# io-ok.net
KiCad netlist of a schematic drawn in EAGLE
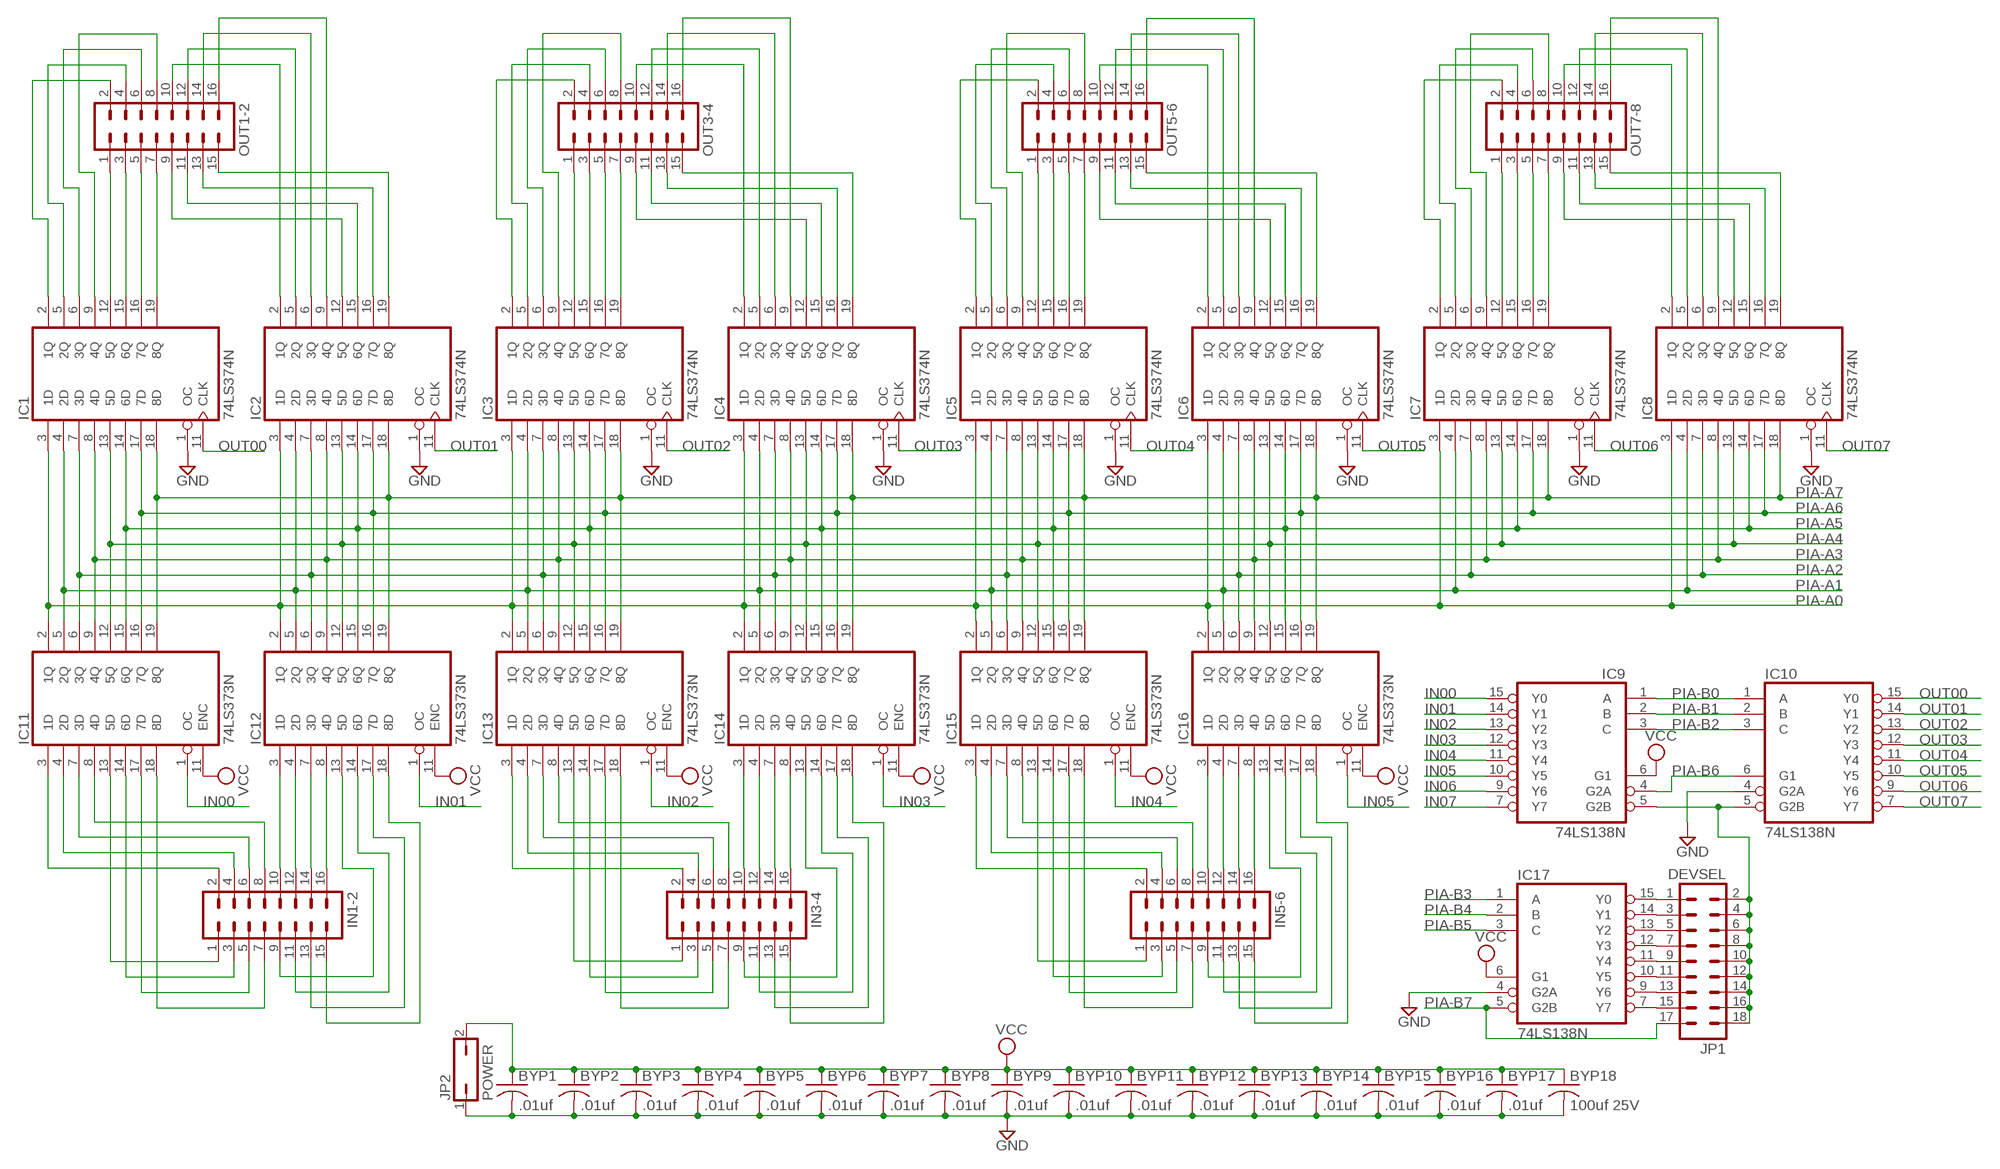
[diagram p0: schematic, sheet 1]
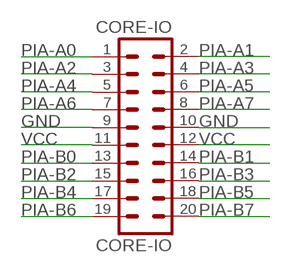
[diagram p1: schematic, sheet 2]

(export (version "E")
  (design (tool "Eeschema 10.0.6"))
  (components
    (comp (ref "CORE-IO")
      (value "CORE-IO")
      (footprint "eagle-import:MA10-2")
      (libsource (lib "eagle-import") (part "MA10-2"))
    )
    (comp (ref "BYP1")
      (value ".01uf")
      (footprint "eagle-import:C050-025X075")
      (libsource (lib "eagle-import") (part "C-US050-025X075"))
    )
    (comp (ref "BYP2")
      (value ".01uf")
      (footprint "eagle-import:C050-025X075")
      (libsource (lib "eagle-import") (part "C-US050-025X075"))
    )
    (comp (ref "BYP3")
      (value ".01uf")
      (footprint "eagle-import:C050-025X075")
      (libsource (lib "eagle-import") (part "C-US050-025X075"))
    )
    (comp (ref "BYP4")
      (value ".01uf")
      (footprint "eagle-import:C050-025X075")
      (libsource (lib "eagle-import") (part "C-US050-025X075"))
    )
    (comp (ref "BYP5")
      (value ".01uf")
      (footprint "eagle-import:C050-025X075")
      (libsource (lib "eagle-import") (part "C-US050-025X075"))
    )
    (comp (ref "BYP6")
      (value ".01uf")
      (footprint "eagle-import:C050-025X075")
      (libsource (lib "eagle-import") (part "C-US050-025X075"))
    )
    (comp (ref "BYP7")
      (value ".01uf")
      (footprint "eagle-import:C050-025X075")
      (libsource (lib "eagle-import") (part "C-US050-025X075"))
    )
    (comp (ref "BYP8")
      (value ".01uf")
      (footprint "eagle-import:C050-025X075")
      (libsource (lib "eagle-import") (part "C-US050-025X075"))
    )
    (comp (ref "BYP9")
      (value ".01uf")
      (footprint "eagle-import:C050-025X075")
      (libsource (lib "eagle-import") (part "C-US050-025X075"))
    )
    (comp (ref "BYP10")
      (value ".01uf")
      (footprint "eagle-import:C050-025X075")
      (libsource (lib "eagle-import") (part "C-US050-025X075"))
    )
    (comp (ref "BYP11")
      (value ".01uf")
      (footprint "eagle-import:C050-025X075")
      (libsource (lib "eagle-import") (part "C-US050-025X075"))
    )
    (comp (ref "BYP12")
      (value ".01uf")
      (footprint "eagle-import:C050-025X075")
      (libsource (lib "eagle-import") (part "C-US050-025X075"))
    )
    (comp (ref "BYP13")
      (value ".01uf")
      (footprint "eagle-import:C050-025X075")
      (libsource (lib "eagle-import") (part "C-US050-025X075"))
    )
    (comp (ref "BYP14")
      (value ".01uf")
      (footprint "eagle-import:C050-025X075")
      (libsource (lib "eagle-import") (part "C-US050-025X075"))
    )
    (comp (ref "BYP15")
      (value ".01uf")
      (footprint "eagle-import:C050-025X075")
      (libsource (lib "eagle-import") (part "C-US050-025X075"))
    )
    (comp (ref "BYP16")
      (value ".01uf")
      (footprint "eagle-import:C050-025X075")
      (libsource (lib "eagle-import") (part "C-US050-025X075"))
    )
    (comp (ref "BYP17")
      (value ".01uf")
      (footprint "eagle-import:C050-025X075")
      (libsource (lib "eagle-import") (part "C-US050-025X075"))
    )
    (comp (ref "BYP18")
      (value "100uf 25V")
      (footprint "eagle-import:C150-064X183")
      (libsource (lib "eagle-import") (part "C-US150-064X183"))
    )
    (comp (ref "IC1")
      (value "74LS374N")
      (footprint "eagle-import:DIL20")
      (libsource (lib "eagle-import") (part "74374NLS"))
    )
    (comp (ref "IC2")
      (value "74LS374N")
      (footprint "eagle-import:DIL20")
      (libsource (lib "eagle-import") (part "74374NLS"))
    )
    (comp (ref "IC3")
      (value "74LS374N")
      (footprint "eagle-import:DIL20")
      (libsource (lib "eagle-import") (part "74374NLS"))
    )
    (comp (ref "IC4")
      (value "74LS374N")
      (footprint "eagle-import:DIL20")
      (libsource (lib "eagle-import") (part "74374NLS"))
    )
    (comp (ref "IC5")
      (value "74LS374N")
      (footprint "eagle-import:DIL20")
      (libsource (lib "eagle-import") (part "74374NLS"))
    )
    (comp (ref "IC6")
      (value "74LS374N")
      (footprint "eagle-import:DIL20")
      (libsource (lib "eagle-import") (part "74374NLS"))
    )
    (comp (ref "IC7")
      (value "74LS374N")
      (footprint "eagle-import:DIL20")
      (libsource (lib "eagle-import") (part "74374NLS"))
    )
    (comp (ref "IC8")
      (value "74LS374N")
      (footprint "eagle-import:DIL20")
      (libsource (lib "eagle-import") (part "74374NLS"))
    )
    (comp (ref "IC9")
      (value "74LS138N")
      (footprint "eagle-import:DIL16")
      (libsource (lib "eagle-import") (part "74138NLS"))
    )
    (comp (ref "IC10")
      (value "74LS138N")
      (footprint "eagle-import:DIL16")
      (libsource (lib "eagle-import") (part "74138NLS"))
    )
    (comp (ref "IC11")
      (value "74LS373N")
      (footprint "eagle-import:DIL20")
      (libsource (lib "eagle-import") (part "74373NLS"))
    )
    (comp (ref "IC12")
      (value "74LS373N")
      (footprint "eagle-import:DIL20")
      (libsource (lib "eagle-import") (part "74373NLS"))
    )
    (comp (ref "IC13")
      (value "74LS373N")
      (footprint "eagle-import:DIL20")
      (libsource (lib "eagle-import") (part "74373NLS"))
    )
    (comp (ref "IC14")
      (value "74LS373N")
      (footprint "eagle-import:DIL20")
      (libsource (lib "eagle-import") (part "74373NLS"))
    )
    (comp (ref "IC15")
      (value "74LS373N")
      (footprint "eagle-import:DIL20")
      (libsource (lib "eagle-import") (part "74373NLS"))
    )
    (comp (ref "IC16")
      (value "74LS373N")
      (footprint "eagle-import:DIL20")
      (libsource (lib "eagle-import") (part "74373NLS"))
    )
    (comp (ref "IC17")
      (value "74LS138N")
      (footprint "eagle-import:DIL16")
      (libsource (lib "eagle-import") (part "74138NLS"))
    )
    (comp (ref "IN1-2")
      (value "MA08-2")
      (footprint "eagle-import:MA08-2")
      (libsource (lib "eagle-import") (part "MA08-2"))
    )
    (comp (ref "IN3-4")
      (value "MA08-2")
      (footprint "eagle-import:MA08-2")
      (libsource (lib "eagle-import") (part "MA08-2"))
    )
    (comp (ref "IN5-6")
      (value "MA08-2")
      (footprint "eagle-import:MA08-2")
      (libsource (lib "eagle-import") (part "MA08-2"))
    )
    (comp (ref "JP1")
      (value "DEVSEL")
      (footprint "eagle-import:MA09-2")
      (libsource (lib "eagle-import") (part "MA09-2"))
    )
    (comp (ref "JP2")
      (value "POWER")
      (footprint "eagle-import:JP1")
      (libsource (lib "eagle-import") (part "JP1Q"))
    )
    (comp (ref "OUT1-2")
      (value "MA08-2")
      (footprint "eagle-import:MA08-2")
      (libsource (lib "eagle-import") (part "MA08-2"))
    )
    (comp (ref "OUT3-4")
      (value "MA08-2")
      (footprint "eagle-import:MA08-2")
      (libsource (lib "eagle-import") (part "MA08-2"))
    )
    (comp (ref "OUT5-6")
      (value "MA08-2")
      (footprint "eagle-import:MA08-2")
      (libsource (lib "eagle-import") (part "MA08-2"))
    )
    (comp (ref "OUT7-8")
      (value "MA08-2")
      (footprint "eagle-import:MA08-2")
      (libsource (lib "eagle-import") (part "MA08-2"))
    )
  )
  (nets
    (net (code "1") (name "GND") (class "Default")
      (node (ref "BYP1") (pin "2") (pinfunction "2_2") (pintype "passive"))
      (node (ref "BYP10") (pin "2") (pinfunction "2_2") (pintype "passive"))
      (node (ref "BYP11") (pin "2") (pinfunction "2_2") (pintype "passive"))
      (node (ref "BYP12") (pin "2") (pinfunction "2_2") (pintype "passive"))
      (node (ref "BYP13") (pin "2") (pinfunction "2_2") (pintype "passive"))
      (node (ref "BYP14") (pin "2") (pinfunction "2_2") (pintype "passive"))
      (node (ref "BYP15") (pin "2") (pinfunction "2_2") (pintype "passive"))
      (node (ref "BYP16") (pin "2") (pinfunction "2_2") (pintype "passive"))
      (node (ref "BYP17") (pin "2") (pinfunction "2_2") (pintype "passive"))
      (node (ref "BYP18") (pin "2") (pinfunction "2_2") (pintype "passive"))
      (node (ref "BYP2") (pin "2") (pinfunction "2_2") (pintype "passive"))
      (node (ref "BYP3") (pin "2") (pinfunction "2_2") (pintype "passive"))
      (node (ref "BYP4") (pin "2") (pinfunction "2_2") (pintype "passive"))
      (node (ref "BYP5") (pin "2") (pinfunction "2_2") (pintype "passive"))
      (node (ref "BYP6") (pin "2") (pinfunction "2_2") (pintype "passive"))
      (node (ref "BYP7") (pin "2") (pinfunction "2_2") (pintype "passive"))
      (node (ref "BYP8") (pin "2") (pinfunction "2_2") (pintype "passive"))
      (node (ref "BYP9") (pin "2") (pinfunction "2_2") (pintype "passive"))
      (node (ref "CORE-IO") (pin "10") (pinfunction "10_10") (pintype "passive"))
      (node (ref "CORE-IO") (pin "9") (pinfunction "9_9") (pintype "passive"))
      (node (ref "IC1") (pin "1") (pinfunction "OC_1") (pintype "input"))
      (node (ref "IC10") (pin "4") (pinfunction "G2A_4") (pintype "input"))
      (node (ref "IC17") (pin "4") (pinfunction "G2A_4") (pintype "input"))
      (node (ref "IC2") (pin "1") (pinfunction "OC_1") (pintype "input"))
      (node (ref "IC3") (pin "1") (pinfunction "OC_1") (pintype "input"))
      (node (ref "IC4") (pin "1") (pinfunction "OC_1") (pintype "input"))
      (node (ref "IC5") (pin "1") (pinfunction "OC_1") (pintype "input"))
      (node (ref "IC6") (pin "1") (pinfunction "OC_1") (pintype "input"))
      (node (ref "IC7") (pin "1") (pinfunction "OC_1") (pintype "input"))
      (node (ref "IC8") (pin "1") (pinfunction "OC_1") (pintype "input"))
      (node (ref "JP2") (pin "1") (pinfunction "1_1") (pintype "passive"))
    )
    (net (code "2") (name "IN00") (class "Default")
      (node (ref "IC11") (pin "1") (pinfunction "OC_1") (pintype "input"))
      (node (ref "IC9") (pin "15") (pinfunction "Y0_15") (pintype "output"))
    )
    (net (code "3") (name "IN01") (class "Default")
      (node (ref "IC12") (pin "1") (pinfunction "OC_1") (pintype "input"))
      (node (ref "IC9") (pin "14") (pinfunction "Y1_14") (pintype "output"))
    )
    (net (code "4") (name "IN02") (class "Default")
      (node (ref "IC13") (pin "1") (pinfunction "OC_1") (pintype "input"))
      (node (ref "IC9") (pin "13") (pinfunction "Y2_13") (pintype "output"))
    )
    (net (code "5") (name "IN03") (class "Default")
      (node (ref "IC14") (pin "1") (pinfunction "OC_1") (pintype "input"))
      (node (ref "IC9") (pin "12") (pinfunction "Y3_12") (pintype "output"))
    )
    (net (code "6") (name "IN04") (class "Default")
      (node (ref "IC15") (pin "1") (pinfunction "OC_1") (pintype "input"))
      (node (ref "IC9") (pin "11") (pinfunction "Y4_11") (pintype "output"))
    )
    (net (code "7") (name "IN05") (class "Default")
      (node (ref "IC16") (pin "1") (pinfunction "OC_1") (pintype "input"))
      (node (ref "IC9") (pin "10") (pinfunction "Y5_10") (pintype "output"))
    )
    (net (code "8") (name "IN06") (class "Default")
      (node (ref "IC9") (pin "9") (pinfunction "Y6_9") (pintype "output"))
    )
    (net (code "9") (name "IN07") (class "Default")
      (node (ref "IC9") (pin "7") (pinfunction "Y7_7") (pintype "output"))
    )
    (net (code "10") (name "Net-(IC1A-1Q)") (class "Default")
      (node (ref "IC1") (pin "2") (pinfunction "1Q_2") (pintype "tri_state"))
      (node (ref "OUT1-2") (pin "2") (pinfunction "2_2") (pintype "passive"))
    )
    (net (code "11") (name "Net-(IC1A-2Q)") (class "Default")
      (node (ref "IC1") (pin "5") (pinfunction "2Q_5") (pintype "tri_state"))
      (node (ref "OUT1-2") (pin "4") (pinfunction "4_4") (pintype "passive"))
    )
    (net (code "12") (name "Net-(IC1A-3Q)") (class "Default")
      (node (ref "IC1") (pin "6") (pinfunction "3Q_6") (pintype "tri_state"))
      (node (ref "OUT1-2") (pin "6") (pinfunction "6_6") (pintype "passive"))
    )
    (net (code "13") (name "Net-(IC1A-4Q)") (class "Default")
      (node (ref "IC1") (pin "9") (pinfunction "4Q_9") (pintype "tri_state"))
      (node (ref "OUT1-2") (pin "8") (pinfunction "8_8") (pintype "passive"))
    )
    (net (code "14") (name "Net-(IC1A-5Q)") (class "Default")
      (node (ref "IC1") (pin "12") (pinfunction "5Q_12") (pintype "tri_state"))
      (node (ref "OUT1-2") (pin "1") (pinfunction "1_1") (pintype "passive"))
    )
    (net (code "15") (name "Net-(IC1A-6Q)") (class "Default")
      (node (ref "IC1") (pin "15") (pinfunction "6Q_15") (pintype "tri_state"))
      (node (ref "OUT1-2") (pin "3") (pinfunction "3_3") (pintype "passive"))
    )
    (net (code "16") (name "Net-(IC1A-7Q)") (class "Default")
      (node (ref "IC1") (pin "16") (pinfunction "7Q_16") (pintype "tri_state"))
      (node (ref "OUT1-2") (pin "5") (pinfunction "5_5") (pintype "passive"))
    )
    (net (code "17") (name "Net-(IC1A-8Q)") (class "Default")
      (node (ref "IC1") (pin "19") (pinfunction "8Q_19") (pintype "tri_state"))
      (node (ref "OUT1-2") (pin "7") (pinfunction "7_7") (pintype "passive"))
    )
    (net (code "18") (name "Net-(IC2A-1Q)") (class "Default")
      (node (ref "IC2") (pin "2") (pinfunction "1Q_2") (pintype "tri_state"))
      (node (ref "OUT1-2") (pin "10") (pinfunction "10_10") (pintype "passive"))
    )
    (net (code "19") (name "Net-(IC2A-2Q)") (class "Default")
      (node (ref "IC2") (pin "5") (pinfunction "2Q_5") (pintype "tri_state"))
      (node (ref "OUT1-2") (pin "12") (pinfunction "12_12") (pintype "passive"))
    )
    (net (code "20") (name "Net-(IC2A-3Q)") (class "Default")
      (node (ref "IC2") (pin "6") (pinfunction "3Q_6") (pintype "tri_state"))
      (node (ref "OUT1-2") (pin "14") (pinfunction "14_14") (pintype "passive"))
    )
    (net (code "21") (name "Net-(IC2A-4Q)") (class "Default")
      (node (ref "IC2") (pin "9") (pinfunction "4Q_9") (pintype "tri_state"))
      (node (ref "OUT1-2") (pin "16") (pinfunction "16_16") (pintype "passive"))
    )
    (net (code "22") (name "Net-(IC2A-5Q)") (class "Default")
      (node (ref "IC2") (pin "12") (pinfunction "5Q_12") (pintype "tri_state"))
      (node (ref "OUT1-2") (pin "9") (pinfunction "9_9") (pintype "passive"))
    )
    (net (code "23") (name "Net-(IC2A-6Q)") (class "Default")
      (node (ref "IC2") (pin "15") (pinfunction "6Q_15") (pintype "tri_state"))
      (node (ref "OUT1-2") (pin "11") (pinfunction "11_11") (pintype "passive"))
    )
    (net (code "24") (name "Net-(IC2A-7Q)") (class "Default")
      (node (ref "IC2") (pin "16") (pinfunction "7Q_16") (pintype "tri_state"))
      (node (ref "OUT1-2") (pin "13") (pinfunction "13_13") (pintype "passive"))
    )
    (net (code "25") (name "Net-(IC2A-8Q)") (class "Default")
      (node (ref "IC2") (pin "19") (pinfunction "8Q_19") (pintype "tri_state"))
      (node (ref "OUT1-2") (pin "15") (pinfunction "15_15") (pintype "passive"))
    )
    (net (code "26") (name "Net-(IC3A-1Q)") (class "Default")
      (node (ref "IC3") (pin "2") (pinfunction "1Q_2") (pintype "tri_state"))
      (node (ref "OUT3-4") (pin "2") (pinfunction "2_2") (pintype "passive"))
    )
    (net (code "27") (name "Net-(IC3A-2Q)") (class "Default")
      (node (ref "IC3") (pin "5") (pinfunction "2Q_5") (pintype "tri_state"))
      (node (ref "OUT3-4") (pin "4") (pinfunction "4_4") (pintype "passive"))
    )
    (net (code "28") (name "Net-(IC3A-3Q)") (class "Default")
      (node (ref "IC3") (pin "6") (pinfunction "3Q_6") (pintype "tri_state"))
      (node (ref "OUT3-4") (pin "6") (pinfunction "6_6") (pintype "passive"))
    )
    (net (code "29") (name "Net-(IC3A-4Q)") (class "Default")
      (node (ref "IC3") (pin "9") (pinfunction "4Q_9") (pintype "tri_state"))
      (node (ref "OUT3-4") (pin "8") (pinfunction "8_8") (pintype "passive"))
    )
    (net (code "30") (name "Net-(IC3A-5Q)") (class "Default")
      (node (ref "IC3") (pin "12") (pinfunction "5Q_12") (pintype "tri_state"))
      (node (ref "OUT3-4") (pin "1") (pinfunction "1_1") (pintype "passive"))
    )
    (net (code "31") (name "Net-(IC3A-6Q)") (class "Default")
      (node (ref "IC3") (pin "15") (pinfunction "6Q_15") (pintype "tri_state"))
      (node (ref "OUT3-4") (pin "3") (pinfunction "3_3") (pintype "passive"))
    )
    (net (code "32") (name "Net-(IC3A-7Q)") (class "Default")
      (node (ref "IC3") (pin "16") (pinfunction "7Q_16") (pintype "tri_state"))
      (node (ref "OUT3-4") (pin "5") (pinfunction "5_5") (pintype "passive"))
    )
    (net (code "33") (name "Net-(IC3A-8Q)") (class "Default")
      (node (ref "IC3") (pin "19") (pinfunction "8Q_19") (pintype "tri_state"))
      (node (ref "OUT3-4") (pin "7") (pinfunction "7_7") (pintype "passive"))
    )
    (net (code "34") (name "Net-(IC4A-1Q)") (class "Default")
      (node (ref "IC4") (pin "2") (pinfunction "1Q_2") (pintype "tri_state"))
      (node (ref "OUT3-4") (pin "10") (pinfunction "10_10") (pintype "passive"))
    )
    (net (code "35") (name "Net-(IC4A-2Q)") (class "Default")
      (node (ref "IC4") (pin "5") (pinfunction "2Q_5") (pintype "tri_state"))
      (node (ref "OUT3-4") (pin "12") (pinfunction "12_12") (pintype "passive"))
    )
    (net (code "36") (name "Net-(IC4A-3Q)") (class "Default")
      (node (ref "IC4") (pin "6") (pinfunction "3Q_6") (pintype "tri_state"))
      (node (ref "OUT3-4") (pin "14") (pinfunction "14_14") (pintype "passive"))
    )
    (net (code "37") (name "Net-(IC4A-4Q)") (class "Default")
      (node (ref "IC4") (pin "9") (pinfunction "4Q_9") (pintype "tri_state"))
      (node (ref "OUT3-4") (pin "16") (pinfunction "16_16") (pintype "passive"))
    )
    (net (code "38") (name "Net-(IC4A-5Q)") (class "Default")
      (node (ref "IC4") (pin "12") (pinfunction "5Q_12") (pintype "tri_state"))
      (node (ref "OUT3-4") (pin "9") (pinfunction "9_9") (pintype "passive"))
    )
    (net (code "39") (name "Net-(IC4A-6Q)") (class "Default")
      (node (ref "IC4") (pin "15") (pinfunction "6Q_15") (pintype "tri_state"))
      (node (ref "OUT3-4") (pin "11") (pinfunction "11_11") (pintype "passive"))
    )
    (net (code "40") (name "Net-(IC4A-7Q)") (class "Default")
      (node (ref "IC4") (pin "16") (pinfunction "7Q_16") (pintype "tri_state"))
      (node (ref "OUT3-4") (pin "13") (pinfunction "13_13") (pintype "passive"))
    )
    (net (code "41") (name "Net-(IC4A-8Q)") (class "Default")
      (node (ref "IC4") (pin "19") (pinfunction "8Q_19") (pintype "tri_state"))
      (node (ref "OUT3-4") (pin "15") (pinfunction "15_15") (pintype "passive"))
    )
    (net (code "42") (name "Net-(IC5A-1Q)") (class "Default")
      (node (ref "IC5") (pin "2") (pinfunction "1Q_2") (pintype "tri_state"))
      (node (ref "OUT5-6") (pin "2") (pinfunction "2_2") (pintype "passive"))
    )
    (net (code "43") (name "Net-(IC5A-2Q)") (class "Default")
      (node (ref "IC5") (pin "5") (pinfunction "2Q_5") (pintype "tri_state"))
      (node (ref "OUT5-6") (pin "4") (pinfunction "4_4") (pintype "passive"))
    )
    (net (code "44") (name "Net-(IC5A-3Q)") (class "Default")
      (node (ref "IC5") (pin "6") (pinfunction "3Q_6") (pintype "tri_state"))
      (node (ref "OUT5-6") (pin "6") (pinfunction "6_6") (pintype "passive"))
    )
    (net (code "45") (name "Net-(IC5A-4Q)") (class "Default")
      (node (ref "IC5") (pin "9") (pinfunction "4Q_9") (pintype "tri_state"))
      (node (ref "OUT5-6") (pin "8") (pinfunction "8_8") (pintype "passive"))
    )
    (net (code "46") (name "Net-(IC5A-5Q)") (class "Default")
      (node (ref "IC5") (pin "12") (pinfunction "5Q_12") (pintype "tri_state"))
      (node (ref "OUT5-6") (pin "1") (pinfunction "1_1") (pintype "passive"))
    )
    (net (code "47") (name "Net-(IC5A-6Q)") (class "Default")
      (node (ref "IC5") (pin "15") (pinfunction "6Q_15") (pintype "tri_state"))
      (node (ref "OUT5-6") (pin "3") (pinfunction "3_3") (pintype "passive"))
    )
    (net (code "48") (name "Net-(IC5A-7Q)") (class "Default")
      (node (ref "IC5") (pin "16") (pinfunction "7Q_16") (pintype "tri_state"))
      (node (ref "OUT5-6") (pin "5") (pinfunction "5_5") (pintype "passive"))
    )
    (net (code "49") (name "Net-(IC5A-8Q)") (class "Default")
      (node (ref "IC5") (pin "19") (pinfunction "8Q_19") (pintype "tri_state"))
      (node (ref "OUT5-6") (pin "7") (pinfunction "7_7") (pintype "passive"))
    )
    (net (code "50") (name "Net-(IC6A-1Q)") (class "Default")
      (node (ref "IC6") (pin "2") (pinfunction "1Q_2") (pintype "tri_state"))
      (node (ref "OUT5-6") (pin "10") (pinfunction "10_10") (pintype "passive"))
    )
    (net (code "51") (name "Net-(IC6A-2Q)") (class "Default")
      (node (ref "IC6") (pin "5") (pinfunction "2Q_5") (pintype "tri_state"))
      (node (ref "OUT5-6") (pin "12") (pinfunction "12_12") (pintype "passive"))
    )
    (net (code "52") (name "Net-(IC6A-3Q)") (class "Default")
      (node (ref "IC6") (pin "6") (pinfunction "3Q_6") (pintype "tri_state"))
      (node (ref "OUT5-6") (pin "14") (pinfunction "14_14") (pintype "passive"))
    )
    (net (code "53") (name "Net-(IC6A-4Q)") (class "Default")
      (node (ref "IC6") (pin "9") (pinfunction "4Q_9") (pintype "tri_state"))
      (node (ref "OUT5-6") (pin "16") (pinfunction "16_16") (pintype "passive"))
    )
    (net (code "54") (name "Net-(IC6A-5Q)") (class "Default")
      (node (ref "IC6") (pin "12") (pinfunction "5Q_12") (pintype "tri_state"))
      (node (ref "OUT5-6") (pin "9") (pinfunction "9_9") (pintype "passive"))
    )
    (net (code "55") (name "Net-(IC6A-6Q)") (class "Default")
      (node (ref "IC6") (pin "15") (pinfunction "6Q_15") (pintype "tri_state"))
      (node (ref "OUT5-6") (pin "11") (pinfunction "11_11") (pintype "passive"))
    )
    (net (code "56") (name "Net-(IC6A-7Q)") (class "Default")
      (node (ref "IC6") (pin "16") (pinfunction "7Q_16") (pintype "tri_state"))
      (node (ref "OUT5-6") (pin "13") (pinfunction "13_13") (pintype "passive"))
    )
    (net (code "57") (name "Net-(IC6A-8Q)") (class "Default")
      (node (ref "IC6") (pin "19") (pinfunction "8Q_19") (pintype "tri_state"))
      (node (ref "OUT5-6") (pin "15") (pinfunction "15_15") (pintype "passive"))
    )
    (net (code "58") (name "Net-(IC7A-1Q)") (class "Default")
      (node (ref "IC7") (pin "2") (pinfunction "1Q_2") (pintype "tri_state"))
      (node (ref "OUT7-8") (pin "2") (pinfunction "2_2") (pintype "passive"))
    )
    (net (code "59") (name "Net-(IC7A-2Q)") (class "Default")
      (node (ref "IC7") (pin "5") (pinfunction "2Q_5") (pintype "tri_state"))
      (node (ref "OUT7-8") (pin "4") (pinfunction "4_4") (pintype "passive"))
    )
    (net (code "60") (name "Net-(IC7A-3Q)") (class "Default")
      (node (ref "IC7") (pin "6") (pinfunction "3Q_6") (pintype "tri_state"))
      (node (ref "OUT7-8") (pin "6") (pinfunction "6_6") (pintype "passive"))
    )
    (net (code "61") (name "Net-(IC7A-4Q)") (class "Default")
      (node (ref "IC7") (pin "9") (pinfunction "4Q_9") (pintype "tri_state"))
      (node (ref "OUT7-8") (pin "8") (pinfunction "8_8") (pintype "passive"))
    )
    (net (code "62") (name "Net-(IC7A-5Q)") (class "Default")
      (node (ref "IC7") (pin "12") (pinfunction "5Q_12") (pintype "tri_state"))
      (node (ref "OUT7-8") (pin "1") (pinfunction "1_1") (pintype "passive"))
    )
    (net (code "63") (name "Net-(IC7A-6Q)") (class "Default")
      (node (ref "IC7") (pin "15") (pinfunction "6Q_15") (pintype "tri_state"))
      (node (ref "OUT7-8") (pin "3") (pinfunction "3_3") (pintype "passive"))
    )
    (net (code "64") (name "Net-(IC7A-7Q)") (class "Default")
      (node (ref "IC7") (pin "16") (pinfunction "7Q_16") (pintype "tri_state"))
      (node (ref "OUT7-8") (pin "5") (pinfunction "5_5") (pintype "passive"))
    )
    (net (code "65") (name "Net-(IC7A-8Q)") (class "Default")
      (node (ref "IC7") (pin "19") (pinfunction "8Q_19") (pintype "tri_state"))
      (node (ref "OUT7-8") (pin "7") (pinfunction "7_7") (pintype "passive"))
    )
    (net (code "66") (name "Net-(IC8A-1Q)") (class "Default")
      (node (ref "IC8") (pin "2") (pinfunction "1Q_2") (pintype "tri_state"))
      (node (ref "OUT7-8") (pin "10") (pinfunction "10_10") (pintype "passive"))
    )
    (net (code "67") (name "Net-(IC8A-2Q)") (class "Default")
      (node (ref "IC8") (pin "5") (pinfunction "2Q_5") (pintype "tri_state"))
      (node (ref "OUT7-8") (pin "12") (pinfunction "12_12") (pintype "passive"))
    )
    (net (code "68") (name "Net-(IC8A-3Q)") (class "Default")
      (node (ref "IC8") (pin "6") (pinfunction "3Q_6") (pintype "tri_state"))
      (node (ref "OUT7-8") (pin "14") (pinfunction "14_14") (pintype "passive"))
    )
    (net (code "69") (name "Net-(IC8A-4Q)") (class "Default")
      (node (ref "IC8") (pin "9") (pinfunction "4Q_9") (pintype "tri_state"))
      (node (ref "OUT7-8") (pin "16") (pinfunction "16_16") (pintype "passive"))
    )
    (net (code "70") (name "Net-(IC8A-5Q)") (class "Default")
      (node (ref "IC8") (pin "12") (pinfunction "5Q_12") (pintype "tri_state"))
      (node (ref "OUT7-8") (pin "9") (pinfunction "9_9") (pintype "passive"))
    )
    (net (code "71") (name "Net-(IC8A-6Q)") (class "Default")
      (node (ref "IC8") (pin "15") (pinfunction "6Q_15") (pintype "tri_state"))
      (node (ref "OUT7-8") (pin "11") (pinfunction "11_11") (pintype "passive"))
    )
    (net (code "72") (name "Net-(IC8A-7Q)") (class "Default")
      (node (ref "IC8") (pin "16") (pinfunction "7Q_16") (pintype "tri_state"))
      (node (ref "OUT7-8") (pin "13") (pinfunction "13_13") (pintype "passive"))
    )
    (net (code "73") (name "Net-(IC8A-8Q)") (class "Default")
      (node (ref "IC8") (pin "19") (pinfunction "8Q_19") (pintype "tri_state"))
      (node (ref "OUT7-8") (pin "15") (pinfunction "15_15") (pintype "passive"))
    )
    (net (code "74") (name "Net-(IC10A-G2B)") (class "Default")
      (node (ref "IC10") (pin "5") (pinfunction "G2B_5") (pintype "input"))
      (node (ref "IC9") (pin "5") (pinfunction "G2B_5") (pintype "input"))
      (node (ref "JP1") (pin "10") (pinfunction "10_10") (pintype "passive"))
      (node (ref "JP1") (pin "12") (pinfunction "12_12") (pintype "passive"))
      (node (ref "JP1") (pin "14") (pinfunction "14_14") (pintype "passive"))
      (node (ref "JP1") (pin "16") (pinfunction "16_16") (pintype "passive"))
      (node (ref "JP1") (pin "18") (pinfunction "18_18") (pintype "passive"))
      (node (ref "JP1") (pin "2") (pinfunction "2_2") (pintype "passive"))
      (node (ref "JP1") (pin "4") (pinfunction "4_4") (pintype "passive"))
      (node (ref "JP1") (pin "6") (pinfunction "6_6") (pintype "passive"))
      (node (ref "JP1") (pin "8") (pinfunction "8_8") (pintype "passive"))
    )
    (net (code "75") (name "Net-(IC11A-1D)") (class "Default")
      (node (ref "IC11") (pin "3") (pinfunction "1D_3") (pintype "input"))
      (node (ref "IN1-2") (pin "2") (pinfunction "2_2") (pintype "passive"))
    )
    (net (code "76") (name "Net-(IC11A-2D)") (class "Default")
      (node (ref "IC11") (pin "4") (pinfunction "2D_4") (pintype "input"))
      (node (ref "IN1-2") (pin "4") (pinfunction "4_4") (pintype "passive"))
    )
    (net (code "77") (name "Net-(IC11A-3D)") (class "Default")
      (node (ref "IC11") (pin "7") (pinfunction "3D_7") (pintype "input"))
      (node (ref "IN1-2") (pin "6") (pinfunction "6_6") (pintype "passive"))
    )
    (net (code "78") (name "Net-(IC11A-4D)") (class "Default")
      (node (ref "IC11") (pin "8") (pinfunction "4D_8") (pintype "input"))
      (node (ref "IN1-2") (pin "8") (pinfunction "8_8") (pintype "passive"))
    )
    (net (code "79") (name "Net-(IC11A-5D)") (class "Default")
      (node (ref "IC11") (pin "13") (pinfunction "5D_13") (pintype "input"))
      (node (ref "IN1-2") (pin "1") (pinfunction "1_1") (pintype "passive"))
    )
    (net (code "80") (name "Net-(IC11A-6D)") (class "Default")
      (node (ref "IC11") (pin "14") (pinfunction "6D_14") (pintype "input"))
      (node (ref "IN1-2") (pin "3") (pinfunction "3_3") (pintype "passive"))
    )
    (net (code "81") (name "Net-(IC11A-7D)") (class "Default")
      (node (ref "IC11") (pin "17") (pinfunction "7D_17") (pintype "input"))
      (node (ref "IN1-2") (pin "5") (pinfunction "5_5") (pintype "passive"))
    )
    (net (code "82") (name "Net-(IC11A-8D)") (class "Default")
      (node (ref "IC11") (pin "18") (pinfunction "8D_18") (pintype "input"))
      (node (ref "IN1-2") (pin "7") (pinfunction "7_7") (pintype "passive"))
    )
    (net (code "83") (name "Net-(IC12A-1D)") (class "Default")
      (node (ref "IC12") (pin "3") (pinfunction "1D_3") (pintype "input"))
      (node (ref "IN1-2") (pin "10") (pinfunction "10_10") (pintype "passive"))
    )
    (net (code "84") (name "Net-(IC12A-2D)") (class "Default")
      (node (ref "IC12") (pin "4") (pinfunction "2D_4") (pintype "input"))
      (node (ref "IN1-2") (pin "12") (pinfunction "12_12") (pintype "passive"))
    )
    (net (code "85") (name "Net-(IC12A-3D)") (class "Default")
      (node (ref "IC12") (pin "7") (pinfunction "3D_7") (pintype "input"))
      (node (ref "IN1-2") (pin "14") (pinfunction "14_14") (pintype "passive"))
    )
    (net (code "86") (name "Net-(IC12A-4D)") (class "Default")
      (node (ref "IC12") (pin "8") (pinfunction "4D_8") (pintype "input"))
      (node (ref "IN1-2") (pin "16") (pinfunction "16_16") (pintype "passive"))
    )
    (net (code "87") (name "Net-(IC12A-5D)") (class "Default")
      (node (ref "IC12") (pin "13") (pinfunction "5D_13") (pintype "input"))
      (node (ref "IN1-2") (pin "9") (pinfunction "9_9") (pintype "passive"))
    )
    (net (code "88") (name "Net-(IC12A-6D)") (class "Default")
      (node (ref "IC12") (pin "14") (pinfunction "6D_14") (pintype "input"))
      (node (ref "IN1-2") (pin "11") (pinfunction "11_11") (pintype "passive"))
    )
    (net (code "89") (name "Net-(IC12A-7D)") (class "Default")
      (node (ref "IC12") (pin "17") (pinfunction "7D_17") (pintype "input"))
      (node (ref "IN1-2") (pin "13") (pinfunction "13_13") (pintype "passive"))
    )
    (net (code "90") (name "Net-(IC12A-8D)") (class "Default")
      (node (ref "IC12") (pin "18") (pinfunction "8D_18") (pintype "input"))
      (node (ref "IN1-2") (pin "15") (pinfunction "15_15") (pintype "passive"))
    )
    (net (code "91") (name "Net-(IC13A-1D)") (class "Default")
      (node (ref "IC13") (pin "3") (pinfunction "1D_3") (pintype "input"))
      (node (ref "IN3-4") (pin "2") (pinfunction "2_2") (pintype "passive"))
    )
    (net (code "92") (name "Net-(IC13A-2D)") (class "Default")
      (node (ref "IC13") (pin "4") (pinfunction "2D_4") (pintype "input"))
      (node (ref "IN3-4") (pin "4") (pinfunction "4_4") (pintype "passive"))
    )
    (net (code "93") (name "Net-(IC13A-3D)") (class "Default")
      (node (ref "IC13") (pin "7") (pinfunction "3D_7") (pintype "input"))
      (node (ref "IN3-4") (pin "6") (pinfunction "6_6") (pintype "passive"))
    )
    (net (code "94") (name "Net-(IC13A-4D)") (class "Default")
      (node (ref "IC13") (pin "8") (pinfunction "4D_8") (pintype "input"))
      (node (ref "IN3-4") (pin "8") (pinfunction "8_8") (pintype "passive"))
    )
    (net (code "95") (name "Net-(IC13A-5D)") (class "Default")
      (node (ref "IC13") (pin "13") (pinfunction "5D_13") (pintype "input"))
      (node (ref "IN3-4") (pin "1") (pinfunction "1_1") (pintype "passive"))
    )
    (net (code "96") (name "Net-(IC13A-6D)") (class "Default")
      (node (ref "IC13") (pin "14") (pinfunction "6D_14") (pintype "input"))
      (node (ref "IN3-4") (pin "3") (pinfunction "3_3") (pintype "passive"))
    )
    (net (code "97") (name "Net-(IC13A-7D)") (class "Default")
      (node (ref "IC13") (pin "17") (pinfunction "7D_17") (pintype "input"))
      (node (ref "IN3-4") (pin "5") (pinfunction "5_5") (pintype "passive"))
    )
    (net (code "98") (name "Net-(IC13A-8D)") (class "Default")
      (node (ref "IC13") (pin "18") (pinfunction "8D_18") (pintype "input"))
      (node (ref "IN3-4") (pin "7") (pinfunction "7_7") (pintype "passive"))
    )
    (net (code "99") (name "Net-(IC14A-1D)") (class "Default")
      (node (ref "IC14") (pin "3") (pinfunction "1D_3") (pintype "input"))
      (node (ref "IN3-4") (pin "10") (pinfunction "10_10") (pintype "passive"))
    )
    (net (code "100") (name "Net-(IC14A-2D)") (class "Default")
      (node (ref "IC14") (pin "4") (pinfunction "2D_4") (pintype "input"))
      (node (ref "IN3-4") (pin "12") (pinfunction "12_12") (pintype "passive"))
    )
    (net (code "101") (name "Net-(IC14A-3D)") (class "Default")
      (node (ref "IC14") (pin "7") (pinfunction "3D_7") (pintype "input"))
      (node (ref "IN3-4") (pin "14") (pinfunction "14_14") (pintype "passive"))
    )
    (net (code "102") (name "Net-(IC14A-4D)") (class "Default")
      (node (ref "IC14") (pin "8") (pinfunction "4D_8") (pintype "input"))
      (node (ref "IN3-4") (pin "16") (pinfunction "16_16") (pintype "passive"))
    )
    (net (code "103") (name "Net-(IC14A-5D)") (class "Default")
      (node (ref "IC14") (pin "13") (pinfunction "5D_13") (pintype "input"))
      (node (ref "IN3-4") (pin "9") (pinfunction "9_9") (pintype "passive"))
    )
    (net (code "104") (name "Net-(IC14A-6D)") (class "Default")
      (node (ref "IC14") (pin "14") (pinfunction "6D_14") (pintype "input"))
      (node (ref "IN3-4") (pin "11") (pinfunction "11_11") (pintype "passive"))
    )
    (net (code "105") (name "Net-(IC14A-7D)") (class "Default")
      (node (ref "IC14") (pin "17") (pinfunction "7D_17") (pintype "input"))
      (node (ref "IN3-4") (pin "13") (pinfunction "13_13") (pintype "passive"))
    )
    (net (code "106") (name "Net-(IC14A-8D)") (class "Default")
      (node (ref "IC14") (pin "18") (pinfunction "8D_18") (pintype "input"))
      (node (ref "IN3-4") (pin "15") (pinfunction "15_15") (pintype "passive"))
    )
    (net (code "107") (name "Net-(IC15A-1D)") (class "Default")
      (node (ref "IC15") (pin "3") (pinfunction "1D_3") (pintype "input"))
      (node (ref "IN5-6") (pin "2") (pinfunction "2_2") (pintype "passive"))
    )
    (net (code "108") (name "Net-(IC15A-2D)") (class "Default")
      (node (ref "IC15") (pin "4") (pinfunction "2D_4") (pintype "input"))
      (node (ref "IN5-6") (pin "4") (pinfunction "4_4") (pintype "passive"))
    )
    (net (code "109") (name "Net-(IC15A-3D)") (class "Default")
      (node (ref "IC15") (pin "7") (pinfunction "3D_7") (pintype "input"))
      (node (ref "IN5-6") (pin "6") (pinfunction "6_6") (pintype "passive"))
    )
    (net (code "110") (name "Net-(IC15A-4D)") (class "Default")
      (node (ref "IC15") (pin "8") (pinfunction "4D_8") (pintype "input"))
      (node (ref "IN5-6") (pin "8") (pinfunction "8_8") (pintype "passive"))
    )
    (net (code "111") (name "Net-(IC15A-5D)") (class "Default")
      (node (ref "IC15") (pin "13") (pinfunction "5D_13") (pintype "input"))
      (node (ref "IN5-6") (pin "1") (pinfunction "1_1") (pintype "passive"))
    )
    (net (code "112") (name "Net-(IC15A-6D)") (class "Default")
      (node (ref "IC15") (pin "14") (pinfunction "6D_14") (pintype "input"))
      (node (ref "IN5-6") (pin "3") (pinfunction "3_3") (pintype "passive"))
    )
    (net (code "113") (name "Net-(IC15A-7D)") (class "Default")
      (node (ref "IC15") (pin "17") (pinfunction "7D_17") (pintype "input"))
      (node (ref "IN5-6") (pin "5") (pinfunction "5_5") (pintype "passive"))
    )
    (net (code "114") (name "Net-(IC15A-8D)") (class "Default")
      (node (ref "IC15") (pin "18") (pinfunction "8D_18") (pintype "input"))
      (node (ref "IN5-6") (pin "7") (pinfunction "7_7") (pintype "passive"))
    )
    (net (code "115") (name "Net-(IC16A-1D)") (class "Default")
      (node (ref "IC16") (pin "3") (pinfunction "1D_3") (pintype "input"))
      (node (ref "IN5-6") (pin "10") (pinfunction "10_10") (pintype "passive"))
    )
    (net (code "116") (name "Net-(IC16A-2D)") (class "Default")
      (node (ref "IC16") (pin "4") (pinfunction "2D_4") (pintype "input"))
      (node (ref "IN5-6") (pin "12") (pinfunction "12_12") (pintype "passive"))
    )
    (net (code "117") (name "Net-(IC16A-3D)") (class "Default")
      (node (ref "IC16") (pin "7") (pinfunction "3D_7") (pintype "input"))
      (node (ref "IN5-6") (pin "14") (pinfunction "14_14") (pintype "passive"))
    )
    (net (code "118") (name "Net-(IC16A-4D)") (class "Default")
      (node (ref "IC16") (pin "8") (pinfunction "4D_8") (pintype "input"))
      (node (ref "IN5-6") (pin "16") (pinfunction "16_16") (pintype "passive"))
    )
    (net (code "119") (name "Net-(IC16A-5D)") (class "Default")
      (node (ref "IC16") (pin "13") (pinfunction "5D_13") (pintype "input"))
      (node (ref "IN5-6") (pin "9") (pinfunction "9_9") (pintype "passive"))
    )
    (net (code "120") (name "Net-(IC16A-6D)") (class "Default")
      (node (ref "IC16") (pin "14") (pinfunction "6D_14") (pintype "input"))
      (node (ref "IN5-6") (pin "11") (pinfunction "11_11") (pintype "passive"))
    )
    (net (code "121") (name "Net-(IC16A-7D)") (class "Default")
      (node (ref "IC16") (pin "17") (pinfunction "7D_17") (pintype "input"))
      (node (ref "IN5-6") (pin "13") (pinfunction "13_13") (pintype "passive"))
    )
    (net (code "122") (name "Net-(IC16A-8D)") (class "Default")
      (node (ref "IC16") (pin "18") (pinfunction "8D_18") (pintype "input"))
      (node (ref "IN5-6") (pin "15") (pinfunction "15_15") (pintype "passive"))
    )
    (net (code "123") (name "Net-(IC17A-Y0)") (class "Default")
      (node (ref "IC17") (pin "15") (pinfunction "Y0_15") (pintype "output"))
      (node (ref "JP1") (pin "1") (pinfunction "1_1") (pintype "passive"))
    )
    (net (code "124") (name "Net-(IC17A-Y1)") (class "Default")
      (node (ref "IC17") (pin "14") (pinfunction "Y1_14") (pintype "output"))
      (node (ref "JP1") (pin "3") (pinfunction "3_3") (pintype "passive"))
    )
    (net (code "125") (name "Net-(IC17A-Y2)") (class "Default")
      (node (ref "IC17") (pin "13") (pinfunction "Y2_13") (pintype "output"))
      (node (ref "JP1") (pin "5") (pinfunction "5_5") (pintype "passive"))
    )
    (net (code "126") (name "Net-(IC17A-Y3)") (class "Default")
      (node (ref "IC17") (pin "12") (pinfunction "Y3_12") (pintype "output"))
      (node (ref "JP1") (pin "7") (pinfunction "7_7") (pintype "passive"))
    )
    (net (code "127") (name "Net-(IC17A-Y4)") (class "Default")
      (node (ref "IC17") (pin "11") (pinfunction "Y4_11") (pintype "output"))
      (node (ref "JP1") (pin "9") (pinfunction "9_9") (pintype "passive"))
    )
    (net (code "128") (name "Net-(IC17A-Y5)") (class "Default")
      (node (ref "IC17") (pin "10") (pinfunction "Y5_10") (pintype "output"))
      (node (ref "JP1") (pin "11") (pinfunction "11_11") (pintype "passive"))
    )
    (net (code "129") (name "Net-(IC17A-Y6)") (class "Default")
      (node (ref "IC17") (pin "9") (pinfunction "Y6_9") (pintype "output"))
      (node (ref "JP1") (pin "13") (pinfunction "13_13") (pintype "passive"))
    )
    (net (code "130") (name "Net-(IC17A-Y7)") (class "Default")
      (node (ref "IC17") (pin "7") (pinfunction "Y7_7") (pintype "output"))
      (node (ref "JP1") (pin "15") (pinfunction "15_15") (pintype "passive"))
    )
    (net (code "131") (name "OUT00") (class "Default")
      (node (ref "IC1") (pin "11") (pinfunction "CLK_11") (pintype "input"))
      (node (ref "IC10") (pin "15") (pinfunction "Y0_15") (pintype "output"))
    )
    (net (code "132") (name "OUT01") (class "Default")
      (node (ref "IC10") (pin "14") (pinfunction "Y1_14") (pintype "output"))
      (node (ref "IC2") (pin "11") (pinfunction "CLK_11") (pintype "input"))
    )
    (net (code "133") (name "OUT02") (class "Default")
      (node (ref "IC10") (pin "13") (pinfunction "Y2_13") (pintype "output"))
      (node (ref "IC3") (pin "11") (pinfunction "CLK_11") (pintype "input"))
    )
    (net (code "134") (name "OUT03") (class "Default")
      (node (ref "IC10") (pin "12") (pinfunction "Y3_12") (pintype "output"))
      (node (ref "IC4") (pin "11") (pinfunction "CLK_11") (pintype "input"))
    )
    (net (code "135") (name "OUT04") (class "Default")
      (node (ref "IC10") (pin "11") (pinfunction "Y4_11") (pintype "output"))
      (node (ref "IC5") (pin "11") (pinfunction "CLK_11") (pintype "input"))
    )
    (net (code "136") (name "OUT05") (class "Default")
      (node (ref "IC10") (pin "10") (pinfunction "Y5_10") (pintype "output"))
      (node (ref "IC6") (pin "11") (pinfunction "CLK_11") (pintype "input"))
    )
    (net (code "137") (name "OUT06") (class "Default")
      (node (ref "IC10") (pin "9") (pinfunction "Y6_9") (pintype "output"))
      (node (ref "IC7") (pin "11") (pinfunction "CLK_11") (pintype "input"))
    )
    (net (code "138") (name "OUT07") (class "Default")
      (node (ref "IC10") (pin "7") (pinfunction "Y7_7") (pintype "output"))
      (node (ref "IC8") (pin "11") (pinfunction "CLK_11") (pintype "input"))
    )
    (net (code "139") (name "PIA-A0") (class "Default")
      (node (ref "CORE-IO") (pin "1") (pinfunction "1_1") (pintype "passive"))
      (node (ref "IC1") (pin "3") (pinfunction "1D_3") (pintype "input"))
      (node (ref "IC11") (pin "2") (pinfunction "1Q_2") (pintype "tri_state"))
      (node (ref "IC12") (pin "2") (pinfunction "1Q_2") (pintype "tri_state"))
      (node (ref "IC13") (pin "2") (pinfunction "1Q_2") (pintype "tri_state"))
      (node (ref "IC14") (pin "2") (pinfunction "1Q_2") (pintype "tri_state"))
      (node (ref "IC15") (pin "2") (pinfunction "1Q_2") (pintype "tri_state"))
      (node (ref "IC16") (pin "2") (pinfunction "1Q_2") (pintype "tri_state"))
      (node (ref "IC2") (pin "3") (pinfunction "1D_3") (pintype "input"))
      (node (ref "IC3") (pin "3") (pinfunction "1D_3") (pintype "input"))
      (node (ref "IC4") (pin "3") (pinfunction "1D_3") (pintype "input"))
      (node (ref "IC5") (pin "3") (pinfunction "1D_3") (pintype "input"))
      (node (ref "IC6") (pin "3") (pinfunction "1D_3") (pintype "input"))
      (node (ref "IC7") (pin "3") (pinfunction "1D_3") (pintype "input"))
      (node (ref "IC8") (pin "3") (pinfunction "1D_3") (pintype "input"))
    )
    (net (code "140") (name "PIA-A1") (class "Default")
      (node (ref "CORE-IO") (pin "2") (pinfunction "2_2") (pintype "passive"))
      (node (ref "IC1") (pin "4") (pinfunction "2D_4") (pintype "input"))
      (node (ref "IC11") (pin "5") (pinfunction "2Q_5") (pintype "tri_state"))
      (node (ref "IC12") (pin "5") (pinfunction "2Q_5") (pintype "tri_state"))
      (node (ref "IC13") (pin "5") (pinfunction "2Q_5") (pintype "tri_state"))
      (node (ref "IC14") (pin "5") (pinfunction "2Q_5") (pintype "tri_state"))
      (node (ref "IC15") (pin "5") (pinfunction "2Q_5") (pintype "tri_state"))
      (node (ref "IC16") (pin "5") (pinfunction "2Q_5") (pintype "tri_state"))
      (node (ref "IC2") (pin "4") (pinfunction "2D_4") (pintype "input"))
      (node (ref "IC3") (pin "4") (pinfunction "2D_4") (pintype "input"))
      (node (ref "IC4") (pin "4") (pinfunction "2D_4") (pintype "input"))
      (node (ref "IC5") (pin "4") (pinfunction "2D_4") (pintype "input"))
      (node (ref "IC6") (pin "4") (pinfunction "2D_4") (pintype "input"))
      (node (ref "IC7") (pin "4") (pinfunction "2D_4") (pintype "input"))
      (node (ref "IC8") (pin "4") (pinfunction "2D_4") (pintype "input"))
    )
    (net (code "141") (name "PIA-A2") (class "Default")
      (node (ref "CORE-IO") (pin "3") (pinfunction "3_3") (pintype "passive"))
      (node (ref "IC1") (pin "7") (pinfunction "3D_7") (pintype "input"))
      (node (ref "IC11") (pin "6") (pinfunction "3Q_6") (pintype "tri_state"))
      (node (ref "IC12") (pin "6") (pinfunction "3Q_6") (pintype "tri_state"))
      (node (ref "IC13") (pin "6") (pinfunction "3Q_6") (pintype "tri_state"))
      (node (ref "IC14") (pin "6") (pinfunction "3Q_6") (pintype "tri_state"))
      (node (ref "IC15") (pin "6") (pinfunction "3Q_6") (pintype "tri_state"))
      (node (ref "IC16") (pin "6") (pinfunction "3Q_6") (pintype "tri_state"))
      (node (ref "IC2") (pin "7") (pinfunction "3D_7") (pintype "input"))
      (node (ref "IC3") (pin "7") (pinfunction "3D_7") (pintype "input"))
      (node (ref "IC4") (pin "7") (pinfunction "3D_7") (pintype "input"))
      (node (ref "IC5") (pin "7") (pinfunction "3D_7") (pintype "input"))
      (node (ref "IC6") (pin "7") (pinfunction "3D_7") (pintype "input"))
      (node (ref "IC7") (pin "7") (pinfunction "3D_7") (pintype "input"))
      (node (ref "IC8") (pin "7") (pinfunction "3D_7") (pintype "input"))
    )
    (net (code "142") (name "PIA-A3") (class "Default")
      (node (ref "CORE-IO") (pin "4") (pinfunction "4_4") (pintype "passive"))
      (node (ref "IC1") (pin "8") (pinfunction "4D_8") (pintype "input"))
      (node (ref "IC11") (pin "9") (pinfunction "4Q_9") (pintype "tri_state"))
      (node (ref "IC12") (pin "9") (pinfunction "4Q_9") (pintype "tri_state"))
      (node (ref "IC13") (pin "9") (pinfunction "4Q_9") (pintype "tri_state"))
      (node (ref "IC14") (pin "9") (pinfunction "4Q_9") (pintype "tri_state"))
      (node (ref "IC15") (pin "9") (pinfunction "4Q_9") (pintype "tri_state"))
      (node (ref "IC16") (pin "9") (pinfunction "4Q_9") (pintype "tri_state"))
      (node (ref "IC2") (pin "8") (pinfunction "4D_8") (pintype "input"))
      (node (ref "IC3") (pin "8") (pinfunction "4D_8") (pintype "input"))
      (node (ref "IC4") (pin "8") (pinfunction "4D_8") (pintype "input"))
      (node (ref "IC5") (pin "8") (pinfunction "4D_8") (pintype "input"))
      (node (ref "IC6") (pin "8") (pinfunction "4D_8") (pintype "input"))
      (node (ref "IC7") (pin "8") (pinfunction "4D_8") (pintype "input"))
      (node (ref "IC8") (pin "8") (pinfunction "4D_8") (pintype "input"))
    )
    (net (code "143") (name "PIA-A4") (class "Default")
      (node (ref "CORE-IO") (pin "5") (pinfunction "5_5") (pintype "passive"))
      (node (ref "IC1") (pin "13") (pinfunction "5D_13") (pintype "input"))
      (node (ref "IC11") (pin "12") (pinfunction "5Q_12") (pintype "tri_state"))
      (node (ref "IC12") (pin "12") (pinfunction "5Q_12") (pintype "tri_state"))
      (node (ref "IC13") (pin "12") (pinfunction "5Q_12") (pintype "tri_state"))
      (node (ref "IC14") (pin "12") (pinfunction "5Q_12") (pintype "tri_state"))
      (node (ref "IC15") (pin "12") (pinfunction "5Q_12") (pintype "tri_state"))
      (node (ref "IC16") (pin "12") (pinfunction "5Q_12") (pintype "tri_state"))
      (node (ref "IC2") (pin "13") (pinfunction "5D_13") (pintype "input"))
      (node (ref "IC3") (pin "13") (pinfunction "5D_13") (pintype "input"))
      (node (ref "IC4") (pin "13") (pinfunction "5D_13") (pintype "input"))
      (node (ref "IC5") (pin "13") (pinfunction "5D_13") (pintype "input"))
      (node (ref "IC6") (pin "13") (pinfunction "5D_13") (pintype "input"))
      (node (ref "IC7") (pin "13") (pinfunction "5D_13") (pintype "input"))
      (node (ref "IC8") (pin "13") (pinfunction "5D_13") (pintype "input"))
    )
    (net (code "144") (name "PIA-A5") (class "Default")
      (node (ref "CORE-IO") (pin "6") (pinfunction "6_6") (pintype "passive"))
      (node (ref "IC1") (pin "14") (pinfunction "6D_14") (pintype "input"))
      (node (ref "IC11") (pin "15") (pinfunction "6Q_15") (pintype "tri_state"))
      (node (ref "IC12") (pin "15") (pinfunction "6Q_15") (pintype "tri_state"))
      (node (ref "IC13") (pin "15") (pinfunction "6Q_15") (pintype "tri_state"))
      (node (ref "IC14") (pin "15") (pinfunction "6Q_15") (pintype "tri_state"))
      (node (ref "IC15") (pin "15") (pinfunction "6Q_15") (pintype "tri_state"))
      (node (ref "IC16") (pin "15") (pinfunction "6Q_15") (pintype "tri_state"))
      (node (ref "IC2") (pin "14") (pinfunction "6D_14") (pintype "input"))
      (node (ref "IC3") (pin "14") (pinfunction "6D_14") (pintype "input"))
      (node (ref "IC4") (pin "14") (pinfunction "6D_14") (pintype "input"))
      (node (ref "IC5") (pin "14") (pinfunction "6D_14") (pintype "input"))
      (node (ref "IC6") (pin "14") (pinfunction "6D_14") (pintype "input"))
      (node (ref "IC7") (pin "14") (pinfunction "6D_14") (pintype "input"))
      (node (ref "IC8") (pin "14") (pinfunction "6D_14") (pintype "input"))
    )
    (net (code "145") (name "PIA-A6") (class "Default")
      (node (ref "CORE-IO") (pin "7") (pinfunction "7_7") (pintype "passive"))
      (node (ref "IC1") (pin "17") (pinfunction "7D_17") (pintype "input"))
      (node (ref "IC11") (pin "16") (pinfunction "7Q_16") (pintype "tri_state"))
      (node (ref "IC12") (pin "16") (pinfunction "7Q_16") (pintype "tri_state"))
      (node (ref "IC13") (pin "16") (pinfunction "7Q_16") (pintype "tri_state"))
      (node (ref "IC14") (pin "16") (pinfunction "7Q_16") (pintype "tri_state"))
      (node (ref "IC15") (pin "16") (pinfunction "7Q_16") (pintype "tri_state"))
      (node (ref "IC16") (pin "16") (pinfunction "7Q_16") (pintype "tri_state"))
      (node (ref "IC2") (pin "17") (pinfunction "7D_17") (pintype "input"))
      (node (ref "IC3") (pin "17") (pinfunction "7D_17") (pintype "input"))
      (node (ref "IC4") (pin "17") (pinfunction "7D_17") (pintype "input"))
      (node (ref "IC5") (pin "17") (pinfunction "7D_17") (pintype "input"))
      (node (ref "IC6") (pin "17") (pinfunction "7D_17") (pintype "input"))
      (node (ref "IC7") (pin "17") (pinfunction "7D_17") (pintype "input"))
      (node (ref "IC8") (pin "17") (pinfunction "7D_17") (pintype "input"))
    )
    (net (code "146") (name "PIA-A7") (class "Default")
      (node (ref "CORE-IO") (pin "8") (pinfunction "8_8") (pintype "passive"))
      (node (ref "IC1") (pin "18") (pinfunction "8D_18") (pintype "input"))
      (node (ref "IC11") (pin "19") (pinfunction "8Q_19") (pintype "tri_state"))
      (node (ref "IC12") (pin "19") (pinfunction "8Q_19") (pintype "tri_state"))
      (node (ref "IC13") (pin "19") (pinfunction "8Q_19") (pintype "tri_state"))
      (node (ref "IC14") (pin "19") (pinfunction "8Q_19") (pintype "tri_state"))
      (node (ref "IC15") (pin "19") (pinfunction "8Q_19") (pintype "tri_state"))
      (node (ref "IC16") (pin "19") (pinfunction "8Q_19") (pintype "tri_state"))
      (node (ref "IC2") (pin "18") (pinfunction "8D_18") (pintype "input"))
      (node (ref "IC3") (pin "18") (pinfunction "8D_18") (pintype "input"))
      (node (ref "IC4") (pin "18") (pinfunction "8D_18") (pintype "input"))
      (node (ref "IC5") (pin "18") (pinfunction "8D_18") (pintype "input"))
      (node (ref "IC6") (pin "18") (pinfunction "8D_18") (pintype "input"))
      (node (ref "IC7") (pin "18") (pinfunction "8D_18") (pintype "input"))
      (node (ref "IC8") (pin "18") (pinfunction "8D_18") (pintype "input"))
    )
    (net (code "147") (name "PIA-B0") (class "Default")
      (node (ref "CORE-IO") (pin "13") (pinfunction "13_13") (pintype "passive"))
      (node (ref "IC10") (pin "1") (pinfunction "A_1") (pintype "input"))
      (node (ref "IC9") (pin "1") (pinfunction "A_1") (pintype "input"))
    )
    (net (code "148") (name "PIA-B1") (class "Default")
      (node (ref "CORE-IO") (pin "14") (pinfunction "14_14") (pintype "passive"))
      (node (ref "IC10") (pin "2") (pinfunction "B_2") (pintype "input"))
      (node (ref "IC9") (pin "2") (pinfunction "B_2") (pintype "input"))
    )
    (net (code "149") (name "PIA-B2") (class "Default")
      (node (ref "CORE-IO") (pin "15") (pinfunction "15_15") (pintype "passive"))
      (node (ref "IC10") (pin "3") (pinfunction "C_3") (pintype "input"))
      (node (ref "IC9") (pin "3") (pinfunction "C_3") (pintype "input"))
    )
    (net (code "150") (name "PIA-B3") (class "Default")
      (node (ref "CORE-IO") (pin "16") (pinfunction "16_16") (pintype "passive"))
      (node (ref "IC17") (pin "1") (pinfunction "A_1") (pintype "input"))
    )
    (net (code "151") (name "PIA-B4") (class "Default")
      (node (ref "CORE-IO") (pin "17") (pinfunction "17_17") (pintype "passive"))
      (node (ref "IC17") (pin "2") (pinfunction "B_2") (pintype "input"))
    )
    (net (code "152") (name "PIA-B5") (class "Default")
      (node (ref "CORE-IO") (pin "18") (pinfunction "18_18") (pintype "passive"))
      (node (ref "IC17") (pin "3") (pinfunction "C_3") (pintype "input"))
    )
    (net (code "153") (name "PIA-B6") (class "Default")
      (node (ref "CORE-IO") (pin "19") (pinfunction "19_19") (pintype "passive"))
      (node (ref "IC10") (pin "6") (pinfunction "G1_6") (pintype "input"))
      (node (ref "IC9") (pin "4") (pinfunction "G2A_4") (pintype "input"))
    )
    (net (code "154") (name "PIA-B7") (class "Default")
      (node (ref "CORE-IO") (pin "20") (pinfunction "20_20") (pintype "passive"))
      (node (ref "IC17") (pin "5") (pinfunction "G2B_5") (pintype "input"))
      (node (ref "JP1") (pin "17") (pinfunction "17_17") (pintype "passive"))
    )
    (net (code "155") (name "VCC") (class "Default")
      (node (ref "BYP1") (pin "1") (pinfunction "1_1") (pintype "passive"))
      (node (ref "BYP10") (pin "1") (pinfunction "1_1") (pintype "passive"))
      (node (ref "BYP11") (pin "1") (pinfunction "1_1") (pintype "passive"))
      (node (ref "BYP12") (pin "1") (pinfunction "1_1") (pintype "passive"))
      (node (ref "BYP13") (pin "1") (pinfunction "1_1") (pintype "passive"))
      (node (ref "BYP14") (pin "1") (pinfunction "1_1") (pintype "passive"))
      (node (ref "BYP15") (pin "1") (pinfunction "1_1") (pintype "passive"))
      (node (ref "BYP16") (pin "1") (pinfunction "1_1") (pintype "passive"))
      (node (ref "BYP17") (pin "1") (pinfunction "1_1") (pintype "passive"))
      (node (ref "BYP18") (pin "1") (pinfunction "1_1") (pintype "passive"))
      (node (ref "BYP2") (pin "1") (pinfunction "1_1") (pintype "passive"))
      (node (ref "BYP3") (pin "1") (pinfunction "1_1") (pintype "passive"))
      (node (ref "BYP4") (pin "1") (pinfunction "1_1") (pintype "passive"))
      (node (ref "BYP5") (pin "1") (pinfunction "1_1") (pintype "passive"))
      (node (ref "BYP6") (pin "1") (pinfunction "1_1") (pintype "passive"))
      (node (ref "BYP7") (pin "1") (pinfunction "1_1") (pintype "passive"))
      (node (ref "BYP8") (pin "1") (pinfunction "1_1") (pintype "passive"))
      (node (ref "BYP9") (pin "1") (pinfunction "1_1") (pintype "passive"))
      (node (ref "CORE-IO") (pin "11") (pinfunction "11_11") (pintype "passive"))
      (node (ref "CORE-IO") (pin "12") (pinfunction "12_12") (pintype "passive"))
      (node (ref "IC11") (pin "11") (pinfunction "ENC_11") (pintype "input"))
      (node (ref "IC12") (pin "11") (pinfunction "ENC_11") (pintype "input"))
      (node (ref "IC13") (pin "11") (pinfunction "ENC_11") (pintype "input"))
      (node (ref "IC14") (pin "11") (pinfunction "ENC_11") (pintype "input"))
      (node (ref "IC15") (pin "11") (pinfunction "ENC_11") (pintype "input"))
      (node (ref "IC16") (pin "11") (pinfunction "ENC_11") (pintype "input"))
      (node (ref "IC17") (pin "6") (pinfunction "G1_6") (pintype "input"))
      (node (ref "IC9") (pin "6") (pinfunction "G1_6") (pintype "input"))
      (node (ref "JP2") (pin "2") (pinfunction "2_2") (pintype "passive"))
    )
  )
)
